# Schematic_SensorTapeMaster_v1.net
KiCad netlist of a schematic drawn in Altium Designer
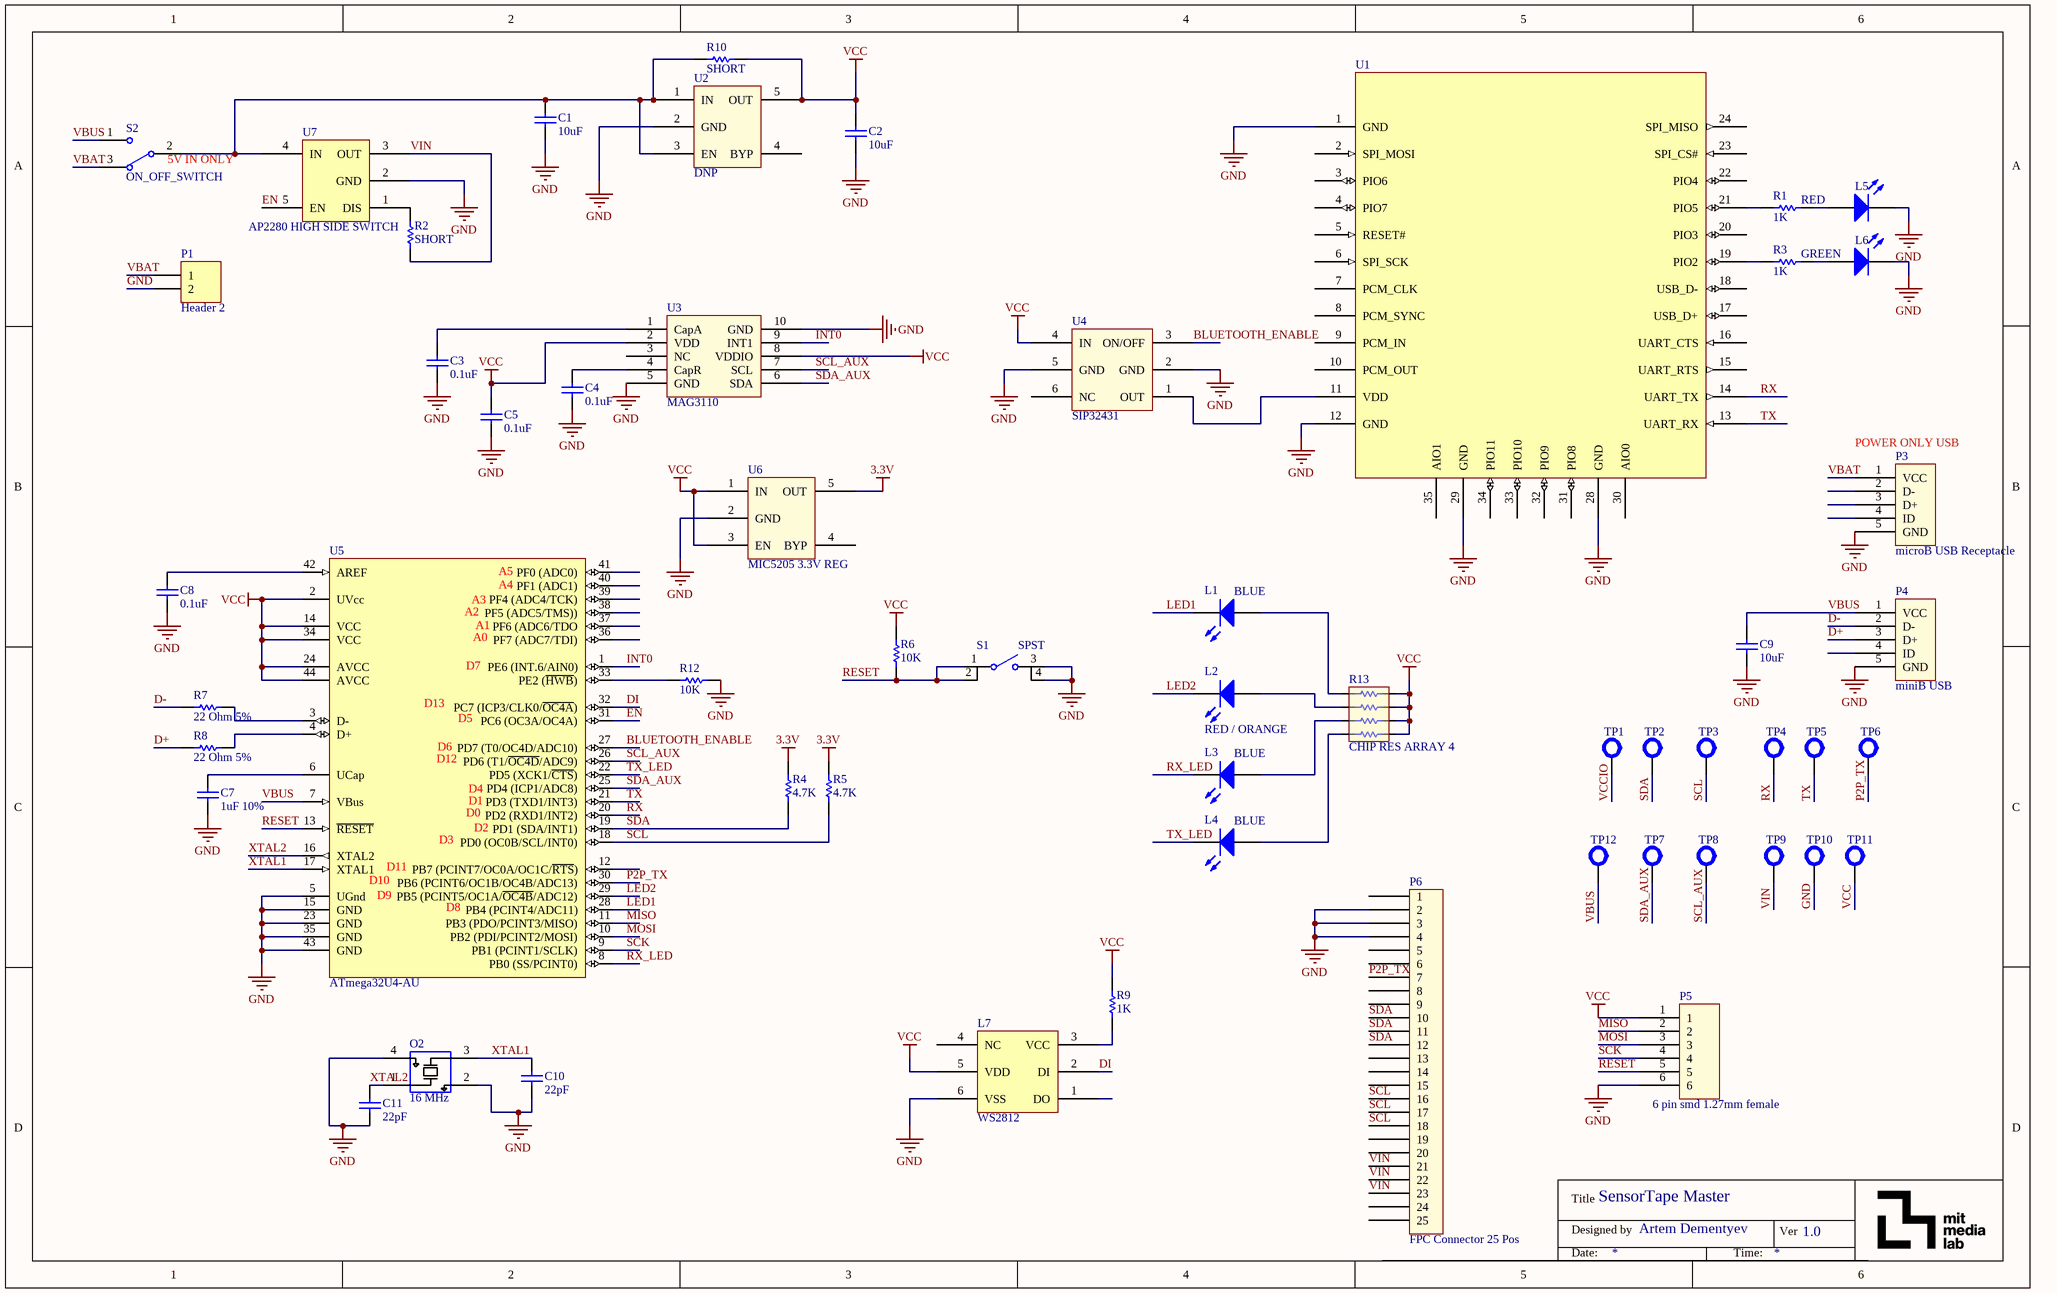
[diagram p0: Schematic_SensorTapeMaster_v1.SchDoc]

(export (version "E")
  (design (tool "Eeschema 10.0.6"))
  (components
    (comp (ref "C1")
      (value "10uF")
      (footprint "0603W")
      (description "SMD Cap 1206")
      (libsource (lib "Artem_Library") (part "Capacitor"))
    )
    (comp (ref "C2")
      (value "10uF")
      (footprint "0603W")
      (description "SMD Cap 1206")
      (libsource (lib "Artem_Library") (part "Capacitor"))
    )
    (comp (ref "C3")
      (value "0.1uF")
      (footprint "0603W")
      (description "SMD Cap 1206")
      (libsource (lib "Artem_Library") (part "Capacitor"))
    )
    (comp (ref "C4")
      (value "0.1uF")
      (footprint "0603W")
      (description "SMD Cap 1206")
      (libsource (lib "Artem_Library") (part "Capacitor"))
    )
    (comp (ref "C5")
      (value "0.1uF")
      (footprint "0603W")
      (description "SMD Cap 1206")
      (libsource (lib "Artem_Library") (part "Capacitor"))
    )
    (comp (ref "C7")
      (value "1uF 10%")
      (footprint "0603W")
      (description "SMD Cap 1206")
      (libsource (lib "Artem_Library") (part "Capacitor"))
    )
    (comp (ref "C8")
      (value "0.1uF")
      (footprint "0603W")
      (description "SMD Cap 1206")
      (libsource (lib "Artem_Library") (part "Capacitor"))
    )
    (comp (ref "C9")
      (value "10uF")
      (footprint "0603W")
      (description "SMD Cap 1206")
      (libsource (lib "Artem_Library") (part "Capacitor"))
    )
    (comp (ref "C10")
      (value "22pF")
      (footprint "0603W")
      (description "SMD Cap 1206")
      (libsource (lib "Artem_Library") (part "Capacitor"))
    )
    (comp (ref "C11")
      (value "22pF")
      (footprint "0603W")
      (description "SMD Cap 1206")
      (libsource (lib "Artem_Library") (part "Capacitor"))
    )
    (comp (ref "L1")
      (value "BLUE")
      (footprint "0603W")
      (description "LED SMD 1206/0603")
      (libsource (lib "Artem_Library") (part "LED"))
    )
    (comp (ref "L2")
      (value "RED / ORANGE")
      (footprint "0603W")
      (description "LED SMD 1206/0603")
      (libsource (lib "Artem_Library") (part "LED"))
    )
    (comp (ref "L3")
      (value "BLUE")
      (footprint "0603W")
      (description "LED SMD 1206/0603")
      (libsource (lib "Artem_Library") (part "LED"))
    )
    (comp (ref "L4")
      (value "BLUE")
      (footprint "0603W")
      (description "LED SMD 1206/0603")
      (libsource (lib "Artem_Library") (part "LED"))
    )
    (comp (ref "L5")
      (value "LED")
      (footprint "0603W")
      (description "LED SMD 1206/0603")
      (libsource (lib "Artem_Library") (part "LED"))
    )
    (comp (ref "L6")
      (value "LED")
      (footprint "0603W")
      (description "LED SMD 1206/0603")
      (libsource (lib "Artem_Library") (part "LED"))
    )
    (comp (ref "L7") (value "WS2812") (footprint "WS2812") (libsource (lib "Artem_Library") (part "WS2812")))
    (comp (ref "O2")
      (value "16 MHz")
      (footprint "CRYSTAL_SMD")
      (description "Surface mount crystal")
      (libsource (lib "Artem_Library") (part "Crystal_SMD"))
    )
    (comp (ref "P1")
      (value "Header 2")
      (footprint "HDR1X2")
      (description "Header, 2-Pin")
      (fields (field (name "PUBLISHER") "Altium Limited"))
      (libsource (lib "Miscellaneous Connectors") (part "Header 2"))
    )
    (comp (ref "P3")
      (value "microB USB Receptacle")
      (footprint "MicroB USB Standarad SMT")
      (fields (field (name "MANUFACTURER") "ZX62-B-5PA(11)"))
      (libsource (lib "Artem_Library") (part "microB USB Receptacle"))
    )
    (comp (ref "P4")
      (value "miniB USB")
      (footprint "UX60SC-MB-5ST")
      (libsource (lib "Artem_Library") (part "miniB USB"))
    )
    (comp (ref "P5")
      (value "6 pin smd 1.27mm female")
      (footprint "6pos 1.27mm")
      (libsource (lib "Artem_Library") (part "6 pin smd 1.27mm female"))
    )
    (comp (ref "P6")
      (value "FPC Connector 25 Pos")
      (footprint "FPC 25 POS")
      (fields (field (name "DIGIKEY PART NUMBER") "A101410CT-ND"))
      (libsource (lib "Artem_Library") (part "FPC Connector 25 Pos"))
    )
    (comp (ref "R1") (value "1K") (footprint "0603W") (libsource (lib "Artem_Library") (part "Resistor")))
    (comp (ref "R2") (value "SHORT") (footprint "0603W") (libsource (lib "Artem_Library") (part "Resistor")))
    (comp (ref "R3") (value "1K") (footprint "0603W") (libsource (lib "Artem_Library") (part "Resistor")))
    (comp (ref "R4") (value "4.7K") (footprint "0603W") (libsource (lib "Artem_Library") (part "Resistor")))
    (comp (ref "R5") (value "4.7K") (footprint "0603W") (libsource (lib "Artem_Library") (part "Resistor")))
    (comp (ref "R6") (value "10K") (footprint "0603W") (libsource (lib "Artem_Library") (part "Resistor")))
    (comp (ref "R7")
      (value "22 Ohm 5%")
      (footprint "0603W")
      (libsource (lib "Artem_Library") (part "Resistor"))
    )
    (comp (ref "R8")
      (value "22 Ohm 5%")
      (footprint "0603W")
      (libsource (lib "Artem_Library") (part "Resistor"))
    )
    (comp (ref "R9") (value "1K") (footprint "0603W") (libsource (lib "Artem_Library") (part "Resistor")))
    (comp (ref "R10") (value "SHORT") (footprint "0603W") (libsource (lib "Artem_Library") (part "Resistor")))
    (comp (ref "R12") (value "10K") (footprint "0603W") (libsource (lib "Artem_Library") (part "Resistor")))
    (comp (ref "R13")
      (value "CHIP RES ARRAY 4")
      (footprint "RES ARRAY 4 1206")
      (libsource (lib "Artem_Library") (part "CHIP RES ARRAY 4"))
    )
    (comp (ref "S1")
      (value "SPST")
      (footprint "EVQQ2 Switch")
      (description "THD Button Switch")
      (libsource (lib "Artem_Library") (part "SPST"))
    )
    (comp (ref "S2")
      (value "ON_OFF_SWITCH")
      (footprint "SS321 Switch")
      (description "SPDT SMD Side Switch")
      (libsource (lib "Artem_Library") (part "ON_OFF_SWITCH"))
    )
    (comp (ref "TP1")
      (value "Test point small")
      (footprint "Test point small")
      (libsource (lib "Artem_Library") (part "Test point small"))
    )
    (comp (ref "TP2")
      (value "Test point small")
      (footprint "Test point small")
      (libsource (lib "Artem_Library") (part "Test point small"))
    )
    (comp (ref "TP3")
      (value "Test point small")
      (footprint "Test point small")
      (libsource (lib "Artem_Library") (part "Test point small"))
    )
    (comp (ref "TP4")
      (value "Test point small")
      (footprint "Test point small")
      (libsource (lib "Artem_Library") (part "Test point small"))
    )
    (comp (ref "TP5")
      (value "Test point small")
      (footprint "Test point small")
      (libsource (lib "Artem_Library") (part "Test point small"))
    )
    (comp (ref "TP6")
      (value "Test point small")
      (footprint "Test point small")
      (libsource (lib "Artem_Library") (part "Test point small"))
    )
    (comp (ref "TP7")
      (value "Test point small")
      (footprint "Test point small")
      (libsource (lib "Artem_Library") (part "Test point small"))
    )
    (comp (ref "TP8")
      (value "Test point small")
      (footprint "Test point small")
      (libsource (lib "Artem_Library") (part "Test point small"))
    )
    (comp (ref "TP9")
      (value "Test point small")
      (footprint "Test point small")
      (libsource (lib "Artem_Library") (part "Test point small"))
    )
    (comp (ref "TP10")
      (value "Test point small")
      (footprint "Test point small")
      (libsource (lib "Artem_Library") (part "Test point small"))
    )
    (comp (ref "TP11")
      (value "Test point small")
      (footprint "Test point small")
      (libsource (lib "Artem_Library") (part "Test point small"))
    )
    (comp (ref "TP12")
      (value "Test point small")
      (footprint "Test point small")
      (libsource (lib "Artem_Library") (part "Test point small"))
    )
    (comp (ref "U1")
      (value "~")
      (footprint "RN-42 LAND")
      (description "Bluetooth serial modem")
      (fields (field (name "DIGIKEY PART NUMBER") "740-1038-ND"))
      (libsource (lib "Artem_Library") (part "RN42"))
    )
    (comp (ref "U2")
      (value "DNP")
      (footprint "SOT-23-5")
      (description "5V LDO SMD")
      (libsource (lib "Artem_Library") (part "MIC5205_VOLTAGE_REG"))
    )
    (comp (ref "U3")
      (value "MAG3110")
      (footprint "10-VFDFN")
      (libsource (lib "Artem_Library") (part "MAG3110"))
    )
    (comp (ref "U4")
      (value "SIP32431")
      (footprint "SOT363")
      (description "High side switch")
      (fields (field (name "DIGIKEY PART NUMBER") "SIP32431DR3-T1GE3CT-ND"))
      (libsource (lib "Artem_Library") (part "SIP32431"))
    )
    (comp (ref "U5")
      (value "ATmega32U4-AU")
      (footprint "44ML_N")
      (fields (field (name "PUBLISHER") "Altium Limited"))
      (libsource (lib "Atmel Microcontroller 8-Bit megaAVR") (part "ATmega32U4-AU"))
    )
    (comp (ref "U6")
      (value "MIC5205 3.3V REG")
      (footprint "SOT-23-5")
      (description "5V LDO SMD")
      (libsource (lib "Artem_Library") (part "MIC5205_VOLTAGE_REG"))
    )
    (comp (ref "U7")
      (value "AP2280 HIGH SIDE SWITCH")
      (footprint "SOT25")
      (description "2A High side switch")
      (libsource (lib "Artem_Library") (part "AP2280 HIGH SIDE SWITCH"))
    )
  )
  (nets
    (net (code "1") (name "/BLUETOOTH_ENABLE") (class "Default")
      (node (ref "U4") (pin "3") (pinfunction "ON/OFF_3") (pintype "passive"))
      (node (ref "U5") (pin "27") (pinfunction "PD7_(T0/OC4D/ADC10)_27") (pintype "bidirectional"))
    )
    (net (code "2") (name "/D+") (class "Default")
      (node (ref "P4") (pin "3") (pinfunction "D+_3") (pintype "passive"))
      (node (ref "R8") (pin "2") (pinfunction "2_2") (pintype "passive"))
    )
    (net (code "3") (name "/D-") (class "Default")
      (node (ref "P4") (pin "2") (pinfunction "D-_2") (pintype "passive"))
      (node (ref "R7") (pin "2") (pinfunction "2_2") (pintype "passive"))
    )
    (net (code "4") (name "/DI") (class "Default")
      (node (ref "L7") (pin "2") (pinfunction "DI_2") (pintype "passive"))
      (node (ref "U5") (pin "32") (pinfunction "PC7_(ICP3/CLK0/~{OC4A})_32") (pintype "bidirectional"))
    )
    (net (code "5") (name "/EN") (class "Default")
      (node (ref "U5") (pin "31") (pinfunction "PC6_(OC3A/OC4A)_31") (pintype "bidirectional"))
      (node (ref "U7") (pin "5") (pinfunction "EN_5") (pintype "passive"))
    )
    (net (code "6") (name "/INT0") (class "Default")
      (node (ref "U3") (pin "9") (pinfunction "INT1_9") (pintype "passive"))
      (node (ref "U5") (pin "1") (pinfunction "PE6_(INT.6/AIN0)_1") (pintype "bidirectional"))
    )
    (net (code "7") (name "/LED1") (class "Default")
      (node (ref "L1") (pin "2") (pinfunction "K_2") (pintype "passive"))
      (node (ref "U5") (pin "28") (pinfunction "PB4_(PCINT4/ADC11)_28") (pintype "bidirectional"))
    )
    (net (code "8") (name "/LED2") (class "Default")
      (node (ref "L2") (pin "2") (pinfunction "K_2") (pintype "passive"))
      (node (ref "U5") (pin "29") (pinfunction "PB5_(PCINT5/OC1A/~{OC4B}/ADC12)_29") (pintype "bidirectional"))
    )
    (net (code "9") (name "/MISO") (class "Default")
      (node (ref "P5") (pin "2") (pinfunction "2_2") (pintype "passive"))
      (node (ref "U5") (pin "11") (pinfunction "PB3_(PDO/PCINT3/MISO)_11") (pintype "bidirectional"))
    )
    (net (code "10") (name "/MOSI") (class "Default")
      (node (ref "P5") (pin "3") (pinfunction "3_3") (pintype "passive"))
      (node (ref "U5") (pin "10") (pinfunction "PB2_(PDI/PCINT2/MOSI)_10") (pintype "bidirectional"))
    )
    (net (code "11") (name "/P2P_TX") (class "Default")
      (node (ref "P6") (pin "7") (pinfunction "7_7") (pintype "passive"))
      (node (ref "TP6") (pin "0") (pinfunction "0_0") (pintype "passive"))
      (node (ref "U5") (pin "30") (pinfunction "PB6_(PCINT6/OC1B/OC4B/ADC13)_30") (pintype "bidirectional"))
    )
    (net (code "12") (name "/RESET") (class "Default")
      (node (ref "P5") (pin "5") (pinfunction "5_5") (pintype "passive"))
      (node (ref "R6") (pin "1") (pinfunction "1_1") (pintype "passive"))
      (node (ref "S1") (pin "1") (pinfunction "COMMON_1") (pintype "passive"))
      (node (ref "S1") (pin "2") (pinfunction "2_2") (pintype "passive"))
      (node (ref "U5") (pin "13") (pinfunction "~{RESET}_13") (pintype "input"))
    )
    (net (code "13") (name "/RX") (class "Default")
      (node (ref "TP4") (pin "0") (pinfunction "0_0") (pintype "passive"))
      (node (ref "U1") (pin "14") (pinfunction "UART_TX_14") (pintype "output"))
      (node (ref "U5") (pin "20") (pinfunction "PD2_(RXD1/INT2)_20") (pintype "bidirectional"))
    )
    (net (code "14") (name "/RX_LED") (class "Default")
      (node (ref "L3") (pin "2") (pinfunction "K_2") (pintype "passive"))
      (node (ref "U5") (pin "8") (pinfunction "PB0_(SS/PCINT0)_8") (pintype "bidirectional"))
    )
    (net (code "15") (name "/SCK") (class "Default")
      (node (ref "P5") (pin "4") (pinfunction "4_4") (pintype "passive"))
      (node (ref "U5") (pin "9") (pinfunction "PB1_(PCINT1/SCLK)_9") (pintype "bidirectional"))
    )
    (net (code "16") (name "/SCL") (class "Default")
      (node (ref "P6") (pin "16") (pinfunction "16_16") (pintype "passive"))
      (node (ref "P6") (pin "17") (pinfunction "17_17") (pintype "passive"))
      (node (ref "P6") (pin "18") (pinfunction "18_18") (pintype "passive"))
      (node (ref "R5") (pin "1") (pinfunction "1_1") (pintype "passive"))
      (node (ref "TP3") (pin "0") (pinfunction "0_0") (pintype "passive"))
      (node (ref "U5") (pin "18") (pinfunction "PD0_(OC0B/SCL/INT0)_18") (pintype "bidirectional"))
    )
    (net (code "17") (name "/SCL_AUX") (class "Default")
      (node (ref "TP8") (pin "0") (pinfunction "0_0") (pintype "passive"))
      (node (ref "U3") (pin "7") (pinfunction "SCL_7") (pintype "passive"))
      (node (ref "U5") (pin "26") (pinfunction "PD6_(T1/~{OC4D}/ADC9)_26") (pintype "bidirectional"))
    )
    (net (code "18") (name "/SDA") (class "Default")
      (node (ref "P6") (pin "10") (pinfunction "10_10") (pintype "passive"))
      (node (ref "P6") (pin "11") (pinfunction "11_11") (pintype "passive"))
      (node (ref "P6") (pin "12") (pinfunction "12_12") (pintype "passive"))
      (node (ref "R4") (pin "2") (pinfunction "2_2") (pintype "passive"))
      (node (ref "TP2") (pin "0") (pinfunction "0_0") (pintype "passive"))
      (node (ref "U5") (pin "19") (pinfunction "PD1_(SDA/INT1)_19") (pintype "bidirectional"))
    )
    (net (code "19") (name "/SDA_AUX") (class "Default")
      (node (ref "TP7") (pin "0") (pinfunction "0_0") (pintype "passive"))
      (node (ref "U3") (pin "6") (pinfunction "SDA_6") (pintype "passive"))
      (node (ref "U5") (pin "25") (pinfunction "PD4_(ICP1/ADC8)_25") (pintype "bidirectional"))
    )
    (net (code "20") (name "/TX") (class "Default")
      (node (ref "TP5") (pin "0") (pinfunction "0_0") (pintype "passive"))
      (node (ref "U1") (pin "13") (pinfunction "UART_RX_13") (pintype "input"))
      (node (ref "U5") (pin "21") (pinfunction "PD3_(TXD1/INT3)_21") (pintype "bidirectional"))
    )
    (net (code "21") (name "/TX_LED") (class "Default")
      (node (ref "L4") (pin "2") (pinfunction "K_2") (pintype "passive"))
      (node (ref "U5") (pin "22") (pinfunction "PD5_(XCK1/~{CTS})_22") (pintype "bidirectional"))
    )
    (net (code "22") (name "/VBAT") (class "Default")
      (node (ref "P1") (pin "1") (pinfunction "1_1") (pintype "passive"))
      (node (ref "P3") (pin "1") (pinfunction "VCC_1") (pintype "passive"))
      (node (ref "S2") (pin "3") (pinfunction "3_3") (pintype "passive"))
    )
    (net (code "23") (name "/VBUS") (class "Default")
      (node (ref "C9") (pin "1") (pinfunction "1_1") (pintype "passive"))
      (node (ref "P4") (pin "1") (pinfunction "VCC_1") (pintype "passive"))
      (node (ref "S2") (pin "1") (pinfunction "1_1") (pintype "passive"))
      (node (ref "TP12") (pin "0") (pinfunction "0_0") (pintype "passive"))
      (node (ref "U5") (pin "7") (pinfunction "VBus_7") (pintype "input"))
    )
    (net (code "24") (name "/VCCIO") (class "Default")
      (node (ref "TP1") (pin "0") (pinfunction "0_0") (pintype "passive"))
    )
    (net (code "25") (name "/VIN") (class "Default")
      (node (ref "P6") (pin "21") (pinfunction "21_21") (pintype "passive"))
      (node (ref "P6") (pin "22") (pinfunction "22_22") (pintype "passive"))
      (node (ref "P6") (pin "23") (pinfunction "23_23") (pintype "passive"))
      (node (ref "R2") (pin "1") (pinfunction "1_1") (pintype "passive"))
      (node (ref "TP9") (pin "0") (pinfunction "0_0") (pintype "passive"))
      (node (ref "U7") (pin "3") (pinfunction "OUT_3") (pintype "passive"))
    )
    (net (code "26") (name "/XTAL1") (class "Default")
      (node (ref "C10") (pin "1") (pinfunction "1_1") (pintype "passive"))
      (node (ref "O2") (pin "3") (pinfunction "XOUT_3") (pintype "passive"))
      (node (ref "U5") (pin "17") (pinfunction "XTAL1_17") (pintype "input"))
    )
    (net (code "27") (name "/XTAL2") (class "Default")
      (node (ref "C11") (pin "1") (pinfunction "1_1") (pintype "passive"))
      (node (ref "O2") (pin "1") (pinfunction "XIN_1") (pintype "passive"))
      (node (ref "U5") (pin "16") (pinfunction "XTAL2_16") (pintype "output"))
    )
    (net (code "28") (name "3.3V") (class "Default")
      (node (ref "R4") (pin "1") (pinfunction "1_1") (pintype "passive"))
      (node (ref "R5") (pin "2") (pinfunction "2_2") (pintype "passive"))
      (node (ref "U6") (pin "5") (pinfunction "OUT_5") (pintype "passive"))
    )
    (net (code "29") (name "GND") (class "Default")
      (node (ref "C1") (pin "1") (pinfunction "1_1") (pintype "passive"))
      (node (ref "C10") (pin "2") (pinfunction "2_2") (pintype "passive"))
      (node (ref "C11") (pin "2") (pinfunction "2_2") (pintype "passive"))
      (node (ref "C2") (pin "1") (pinfunction "1_1") (pintype "passive"))
      (node (ref "C3") (pin "1") (pinfunction "1_1") (pintype "passive"))
      (node (ref "C4") (pin "1") (pinfunction "1_1") (pintype "passive"))
      (node (ref "C5") (pin "1") (pinfunction "1_1") (pintype "passive"))
      (node (ref "C7") (pin "2") (pinfunction "2_2") (pintype "passive"))
      (node (ref "C8") (pin "2") (pinfunction "2_2") (pintype "passive"))
      (node (ref "C9") (pin "2") (pinfunction "2_2") (pintype "passive"))
      (node (ref "L5") (pin "2") (pinfunction "K_2") (pintype "passive"))
      (node (ref "L6") (pin "2") (pinfunction "K_2") (pintype "passive"))
      (node (ref "L7") (pin "6") (pinfunction "VSS_6") (pintype "passive"))
      (node (ref "O2") (pin "2") (pinfunction "Gnd_2") (pintype "passive"))
      (node (ref "O2") (pin "4") (pinfunction "Gnd_4") (pintype "passive"))
      (node (ref "P1") (pin "2") (pinfunction "2_2") (pintype "passive"))
      (node (ref "P3") (pin "5") (pinfunction "GND_5") (pintype "passive"))
      (node (ref "P4") (pin "5") (pinfunction "GND_5") (pintype "passive"))
      (node (ref "P5") (pin "6") (pinfunction "6_6") (pintype "passive"))
      (node (ref "P6") (pin "2") (pinfunction "2_2") (pintype "passive"))
      (node (ref "P6") (pin "3") (pinfunction "3_3") (pintype "passive"))
      (node (ref "P6") (pin "4") (pinfunction "4_4") (pintype "passive"))
      (node (ref "R12") (pin "1") (pinfunction "1_1") (pintype "passive"))
      (node (ref "S1") (pin "3") (pinfunction "3_3") (pintype "passive"))
      (node (ref "S1") (pin "4") (pinfunction "4_4") (pintype "passive"))
      (node (ref "TP10") (pin "0") (pinfunction "0_0") (pintype "passive"))
      (node (ref "U1") (pin "1") (pinfunction "GND_1") (pintype "power_in"))
      (node (ref "U1") (pin "12") (pinfunction "GND_12") (pintype "power_in"))
      (node (ref "U1") (pin "28") (pinfunction "GND_28") (pintype "power_in"))
      (node (ref "U1") (pin "29") (pinfunction "GND_29") (pintype "power_in"))
      (node (ref "U2") (pin "2") (pinfunction "GND_2") (pintype "passive"))
      (node (ref "U3") (pin "10") (pinfunction "GND_10") (pintype "passive"))
      (node (ref "U3") (pin "5") (pinfunction "GND_5") (pintype "passive"))
      (node (ref "U4") (pin "2") (pinfunction "GND_2") (pintype "passive"))
      (node (ref "U4") (pin "5") (pinfunction "GND_5") (pintype "passive"))
      (node (ref "U5") (pin "15") (pinfunction "GND_15") (pintype "power_in"))
      (node (ref "U5") (pin "23") (pinfunction "GND_23") (pintype "power_in"))
      (node (ref "U5") (pin "35") (pinfunction "GND_35") (pintype "power_in"))
      (node (ref "U5") (pin "43") (pinfunction "GND_43") (pintype "power_in"))
      (node (ref "U5") (pin "5") (pinfunction "UGnd_5") (pintype "power_in"))
      (node (ref "U6") (pin "2") (pinfunction "GND_2") (pintype "passive"))
      (node (ref "U7") (pin "2") (pinfunction "GND_2") (pintype "passive"))
    )
    (net (code "30") (name "Net-(L1-A)") (class "Default")
      (node (ref "L1") (pin "1") (pinfunction "A_1") (pintype "passive"))
      (node (ref "R13") (pin "1") (pinfunction "1_1") (pintype "passive"))
    )
    (net (code "31") (name "Net-(L2-A)") (class "Default")
      (node (ref "L2") (pin "1") (pinfunction "A_1") (pintype "passive"))
      (node (ref "R13") (pin "2") (pinfunction "2_2") (pintype "passive"))
    )
    (net (code "32") (name "Net-(L3-A)") (class "Default")
      (node (ref "L3") (pin "1") (pinfunction "A_1") (pintype "passive"))
      (node (ref "R13") (pin "3") (pinfunction "3_3") (pintype "passive"))
    )
    (net (code "33") (name "Net-(L4-A)") (class "Default")
      (node (ref "L4") (pin "1") (pinfunction "A_1") (pintype "passive"))
      (node (ref "R13") (pin "4") (pinfunction "4_4") (pintype "passive"))
    )
    (net (code "34") (name "Net-(L5-A)") (class "Default")
      (node (ref "L5") (pin "1") (pinfunction "A_1") (pintype "passive"))
      (node (ref "R1") (pin "1") (pinfunction "1_1") (pintype "passive"))
    )
    (net (code "35") (name "Net-(L6-A)") (class "Default")
      (node (ref "L6") (pin "1") (pinfunction "A_1") (pintype "passive"))
      (node (ref "R3") (pin "1") (pinfunction "1_1") (pintype "passive"))
    )
    (net (code "36") (name "Net-(L7-VCC)") (class "Default")
      (node (ref "L7") (pin "3") (pinfunction "VCC_3") (pintype "passive"))
      (node (ref "R9") (pin "1") (pinfunction "1_1") (pintype "passive"))
    )
    (net (code "37") (name "Net-(U1-PIO2)") (class "Default")
      (node (ref "R3") (pin "2") (pinfunction "2_2") (pintype "passive"))
      (node (ref "U1") (pin "19") (pinfunction "PIO2_19") (pintype "bidirectional"))
    )
    (net (code "38") (name "Net-(U1-PIO5)") (class "Default")
      (node (ref "R1") (pin "2") (pinfunction "2_2") (pintype "passive"))
      (node (ref "U1") (pin "21") (pinfunction "PIO5_21") (pintype "bidirectional"))
    )
    (net (code "39") (name "Net-(U1-VDD)") (class "Default")
      (node (ref "U1") (pin "11") (pinfunction "VDD_11") (pintype "power_in"))
      (node (ref "U4") (pin "1") (pinfunction "OUT_1") (pintype "passive"))
    )
    (net (code "40") (name "Net-(U2-EN)") (class "Default")
      (node (ref "C1") (pin "2") (pinfunction "2_2") (pintype "passive"))
      (node (ref "R10") (pin "2") (pinfunction "2_2") (pintype "passive"))
      (node (ref "S2") (pin "2") (pinfunction "2_2") (pintype "passive"))
      (node (ref "U2") (pin "1") (pinfunction "IN_1") (pintype "passive"))
      (node (ref "U2") (pin "3") (pinfunction "EN_3") (pintype "passive"))
      (node (ref "U7") (pin "4") (pinfunction "IN_4") (pintype "passive"))
    )
    (net (code "41") (name "Net-(U3-CapA)") (class "Default")
      (node (ref "C3") (pin "2") (pinfunction "2_2") (pintype "passive"))
      (node (ref "U3") (pin "1") (pinfunction "CapA_1") (pintype "passive"))
    )
    (net (code "42") (name "Net-(U3-CapR)") (class "Default")
      (node (ref "C4") (pin "2") (pinfunction "2_2") (pintype "passive"))
      (node (ref "U3") (pin "4") (pinfunction "CapR_4") (pintype "passive"))
    )
    (net (code "43") (name "Net-(U5-AREF)") (class "Default")
      (node (ref "C8") (pin "1") (pinfunction "1_1") (pintype "passive"))
      (node (ref "U5") (pin "42") (pinfunction "AREF_42") (pintype "input"))
    )
    (net (code "44") (name "Net-(U5-D+)") (class "Default")
      (node (ref "R8") (pin "1") (pinfunction "1_1") (pintype "passive"))
      (node (ref "U5") (pin "4") (pinfunction "D+_4") (pintype "bidirectional"))
    )
    (net (code "45") (name "Net-(U5-D-)") (class "Default")
      (node (ref "R7") (pin "1") (pinfunction "1_1") (pintype "passive"))
      (node (ref "U5") (pin "3") (pinfunction "D-_3") (pintype "bidirectional"))
    )
    (net (code "46") (name "Net-(U5-PE2_(~{HWB}))") (class "Default")
      (node (ref "R12") (pin "2") (pinfunction "2_2") (pintype "passive"))
      (node (ref "U5") (pin "33") (pinfunction "PE2_(~{HWB})_33") (pintype "bidirectional"))
    )
    (net (code "47") (name "Net-(U5-UCap)") (class "Default")
      (node (ref "C7") (pin "1") (pinfunction "1_1") (pintype "passive"))
      (node (ref "U5") (pin "6") (pinfunction "UCap_6") (pintype "passive"))
    )
    (net (code "48") (name "Net-(U7-DIS)") (class "Default")
      (node (ref "R2") (pin "2") (pinfunction "2_2") (pintype "passive"))
      (node (ref "U7") (pin "1") (pinfunction "DIS_1") (pintype "passive"))
    )
    (net (code "49") (name "VCC") (class "Default")
      (node (ref "C2") (pin "2") (pinfunction "2_2") (pintype "passive"))
      (node (ref "C5") (pin "2") (pinfunction "2_2") (pintype "passive"))
      (node (ref "L7") (pin "5") (pinfunction "VDD_5") (pintype "passive"))
      (node (ref "P5") (pin "1") (pinfunction "1_1") (pintype "passive"))
      (node (ref "R10") (pin "1") (pinfunction "1_1") (pintype "passive"))
      (node (ref "R13") (pin "5") (pinfunction "5_5") (pintype "passive"))
      (node (ref "R13") (pin "6") (pinfunction "6_6") (pintype "passive"))
      (node (ref "R13") (pin "7") (pinfunction "7_7") (pintype "passive"))
      (node (ref "R13") (pin "8") (pinfunction "8_8") (pintype "passive"))
      (node (ref "R6") (pin "2") (pinfunction "2_2") (pintype "passive"))
      (node (ref "R9") (pin "2") (pinfunction "2_2") (pintype "passive"))
      (node (ref "TP11") (pin "0") (pinfunction "0_0") (pintype "passive"))
      (node (ref "U2") (pin "5") (pinfunction "OUT_5") (pintype "passive"))
      (node (ref "U3") (pin "2") (pinfunction "VDD_2") (pintype "passive"))
      (node (ref "U3") (pin "8") (pinfunction "VDDIO_8") (pintype "passive"))
      (node (ref "U4") (pin "4") (pinfunction "IN_4") (pintype "passive"))
      (node (ref "U5") (pin "14") (pinfunction "VCC_14") (pintype "power_in"))
      (node (ref "U5") (pin "2") (pinfunction "UVcc_2") (pintype "power_in"))
      (node (ref "U5") (pin "24") (pinfunction "AVCC_24") (pintype "power_in"))
      (node (ref "U5") (pin "34") (pinfunction "VCC_34") (pintype "power_in"))
      (node (ref "U5") (pin "44") (pinfunction "AVCC_44") (pintype "power_in"))
      (node (ref "U6") (pin "1") (pinfunction "IN_1") (pintype "passive"))
      (node (ref "U6") (pin "3") (pinfunction "EN_3") (pintype "passive"))
    )
    (net (code "50") (name "unconnected-(L7-DO-Pad1)") (class "Default")
      (node (ref "L7") (pin "1") (pinfunction "DO_1") (pintype "passive"))
    )
    (net (code "51") (name "unconnected-(L7-NC-Pad4)") (class "Default")
      (node (ref "L7") (pin "4") (pinfunction "NC_4") (pintype "passive"))
    )
    (net (code "52") (name "unconnected-(P3-D+-Pad3)") (class "Default")
      (node (ref "P3") (pin "3") (pinfunction "D+_3") (pintype "passive"))
    )
    (net (code "53") (name "unconnected-(P3-D--Pad2)") (class "Default")
      (node (ref "P3") (pin "2") (pinfunction "D-_2") (pintype "passive"))
    )
    (net (code "54") (name "unconnected-(P3-ID-Pad4)") (class "Default")
      (node (ref "P3") (pin "4") (pinfunction "ID_4") (pintype "passive"))
    )
    (net (code "55") (name "unconnected-(P4-ID-Pad4)") (class "Default")
      (node (ref "P4") (pin "4") (pinfunction "ID_4") (pintype "passive"))
    )
    (net (code "56") (name "unconnected-(P6-Pad1)") (class "Default")
      (node (ref "P6") (pin "1") (pinfunction "1_1") (pintype "passive"))
    )
    (net (code "57") (name "unconnected-(P6-Pad5)") (class "Default")
      (node (ref "P6") (pin "5") (pinfunction "5_5") (pintype "passive"))
    )
    (net (code "58") (name "unconnected-(P6-Pad6)") (class "Default")
      (node (ref "P6") (pin "6") (pinfunction "6_6") (pintype "passive"))
    )
    (net (code "59") (name "unconnected-(P6-Pad8)") (class "Default")
      (node (ref "P6") (pin "8") (pinfunction "8_8") (pintype "passive"))
    )
    (net (code "60") (name "unconnected-(P6-Pad9)") (class "Default")
      (node (ref "P6") (pin "9") (pinfunction "9_9") (pintype "passive"))
    )
    (net (code "61") (name "unconnected-(P6-Pad13)") (class "Default")
      (node (ref "P6") (pin "13") (pinfunction "13_13") (pintype "passive"))
    )
    (net (code "62") (name "unconnected-(P6-Pad14)") (class "Default")
      (node (ref "P6") (pin "14") (pinfunction "14_14") (pintype "passive"))
    )
    (net (code "63") (name "unconnected-(P6-Pad15)") (class "Default")
      (node (ref "P6") (pin "15") (pinfunction "15_15") (pintype "passive"))
    )
    (net (code "64") (name "unconnected-(P6-Pad19)") (class "Default")
      (node (ref "P6") (pin "19") (pinfunction "19_19") (pintype "passive"))
    )
    (net (code "65") (name "unconnected-(P6-Pad20)") (class "Default")
      (node (ref "P6") (pin "20") (pinfunction "20_20") (pintype "passive"))
    )
    (net (code "66") (name "unconnected-(P6-Pad24)") (class "Default")
      (node (ref "P6") (pin "24") (pinfunction "24_24") (pintype "passive"))
    )
    (net (code "67") (name "unconnected-(P6-Pad25)") (class "Default")
      (node (ref "P6") (pin "25") (pinfunction "25_25") (pintype "passive"))
    )
    (net (code "68") (name "unconnected-(U1-AIO0-Pad30)") (class "Default")
      (node (ref "U1") (pin "30") (pinfunction "AIO0_30") (pintype "passive"))
    )
    (net (code "69") (name "unconnected-(U1-AIO1-Pad35)") (class "Default")
      (node (ref "U1") (pin "35") (pinfunction "AIO1_35") (pintype "passive"))
    )
    (net (code "70") (name "unconnected-(U1-PCM_CLK-Pad7)") (class "Default")
      (node (ref "U1") (pin "7") (pinfunction "PCM_CLK_7") (pintype "passive"))
    )
    (net (code "71") (name "unconnected-(U1-PCM_IN-Pad9)") (class "Default")
      (node (ref "U1") (pin "9") (pinfunction "PCM_IN_9") (pintype "passive"))
    )
    (net (code "72") (name "unconnected-(U1-PCM_OUT-Pad10)") (class "Default")
      (node (ref "U1") (pin "10") (pinfunction "PCM_OUT_10") (pintype "passive"))
    )
    (net (code "73") (name "unconnected-(U1-PCM_SYNC-Pad8)") (class "Default")
      (node (ref "U1") (pin "8") (pinfunction "PCM_SYNC_8") (pintype "passive"))
    )
    (net (code "74") (name "unconnected-(U1-PIO3-Pad20)") (class "Default")
      (node (ref "U1") (pin "20") (pinfunction "PIO3_20") (pintype "bidirectional"))
    )
    (net (code "75") (name "unconnected-(U1-PIO4-Pad22)") (class "Default")
      (node (ref "U1") (pin "22") (pinfunction "PIO4_22") (pintype "bidirectional"))
    )
    (net (code "76") (name "unconnected-(U1-PIO6-Pad3)") (class "Default")
      (node (ref "U1") (pin "3") (pinfunction "PIO6_3") (pintype "bidirectional"))
    )
    (net (code "77") (name "unconnected-(U1-PIO7-Pad4)") (class "Default")
      (node (ref "U1") (pin "4") (pinfunction "PIO7_4") (pintype "bidirectional"))
    )
    (net (code "78") (name "unconnected-(U1-PIO8-Pad31)") (class "Default")
      (node (ref "U1") (pin "31") (pinfunction "PIO8_31") (pintype "bidirectional"))
    )
    (net (code "79") (name "unconnected-(U1-PIO9-Pad32)") (class "Default")
      (node (ref "U1") (pin "32") (pinfunction "PIO9_32") (pintype "bidirectional"))
    )
    (net (code "80") (name "unconnected-(U1-PIO10-Pad33)") (class "Default")
      (node (ref "U1") (pin "33") (pinfunction "PIO10_33") (pintype "bidirectional"))
    )
    (net (code "81") (name "unconnected-(U1-PIO11-Pad34)") (class "Default")
      (node (ref "U1") (pin "34") (pinfunction "PIO11_34") (pintype "bidirectional"))
    )
    (net (code "82") (name "unconnected-(U1-RESET#-Pad5)") (class "Default")
      (node (ref "U1") (pin "5") (pinfunction "RESET#_5") (pintype "input"))
    )
    (net (code "83") (name "unconnected-(U1-SPI_CS#-Pad23)") (class "Default")
      (node (ref "U1") (pin "23") (pinfunction "SPI_CS#_23") (pintype "input"))
    )
    (net (code "84") (name "unconnected-(U1-SPI_MISO-Pad24)") (class "Default")
      (node (ref "U1") (pin "24") (pinfunction "SPI_MISO_24") (pintype "output"))
    )
    (net (code "85") (name "unconnected-(U1-SPI_MOSI-Pad2)") (class "Default")
      (node (ref "U1") (pin "2") (pinfunction "SPI_MOSI_2") (pintype "input"))
    )
    (net (code "86") (name "unconnected-(U1-SPI_SCK-Pad6)") (class "Default")
      (node (ref "U1") (pin "6") (pinfunction "SPI_SCK_6") (pintype "input"))
    )
    (net (code "87") (name "unconnected-(U1-UART_CTS-Pad16)") (class "Default")
      (node (ref "U1") (pin "16") (pinfunction "UART_CTS_16") (pintype "input"))
    )
    (net (code "88") (name "unconnected-(U1-UART_RTS-Pad15)") (class "Default")
      (node (ref "U1") (pin "15") (pinfunction "UART_RTS_15") (pintype "output"))
    )
    (net (code "89") (name "unconnected-(U1-USB_D+-Pad17)") (class "Default")
      (node (ref "U1") (pin "17") (pinfunction "USB_D+_17") (pintype "bidirectional"))
    )
    (net (code "90") (name "unconnected-(U1-USB_D--Pad18)") (class "Default")
      (node (ref "U1") (pin "18") (pinfunction "USB_D-_18") (pintype "bidirectional"))
    )
    (net (code "91") (name "unconnected-(U2-BYP-Pad4)") (class "Default")
      (node (ref "U2") (pin "4") (pinfunction "BYP_4") (pintype "passive"))
    )
    (net (code "92") (name "unconnected-(U3-NC-Pad3)") (class "Default")
      (node (ref "U3") (pin "3") (pinfunction "NC_3") (pintype "passive"))
    )
    (net (code "93") (name "unconnected-(U4-NC-Pad6)") (class "Default")
      (node (ref "U4") (pin "6") (pinfunction "NC_6") (pintype "passive"))
    )
    (net (code "94") (name "unconnected-(U5-PB7_(PCINT7{slash}OC0A{slash}OC1C{slash}~{RTS})-Pad12)") (class "Default")
      (node (ref "U5") (pin "12") (pinfunction "PB7_(PCINT7/OC0A/OC1C/~{RTS})_12") (pintype "bidirectional"))
    )
    (net (code "95") (name "unconnected-(U5-PF0_(ADC0)-Pad41)") (class "Default")
      (node (ref "U5") (pin "41") (pinfunction "PF0_(ADC0)_41") (pintype "bidirectional"))
    )
    (net (code "96") (name "unconnected-(U5-PF1_(ADC1)-Pad40)") (class "Default")
      (node (ref "U5") (pin "40") (pinfunction "PF1_(ADC1)_40") (pintype "bidirectional"))
    )
    (net (code "97") (name "unconnected-(U5-PF4_(ADC4{slash}TCK)-Pad39)") (class "Default")
      (node (ref "U5") (pin "39") (pinfunction "PF4_(ADC4/TCK)_39") (pintype "bidirectional"))
    )
    (net (code "98") (name "unconnected-(U5-PF5_(ADC5{slash}TMS))-Pad38)") (class "Default")
      (node (ref "U5") (pin "38") (pinfunction "PF5_(ADC5/TMS))_38") (pintype "bidirectional"))
    )
    (net (code "99") (name "unconnected-(U5-PF6_(ADC6{slash}TDO-Pad37)") (class "Default")
      (node (ref "U5") (pin "37") (pinfunction "PF6_(ADC6/TDO_37") (pintype "bidirectional"))
    )
    (net (code "100") (name "unconnected-(U5-PF7_(ADC7{slash}TDI)-Pad36)") (class "Default")
      (node (ref "U5") (pin "36") (pinfunction "PF7_(ADC7/TDI)_36") (pintype "bidirectional"))
    )
    (net (code "101") (name "unconnected-(U6-BYP-Pad4)") (class "Default")
      (node (ref "U6") (pin "4") (pinfunction "BYP_4") (pintype "passive"))
    )
  )
)
